# motherboard.net
KiCad netlist of a schematic drawn in EAGLE
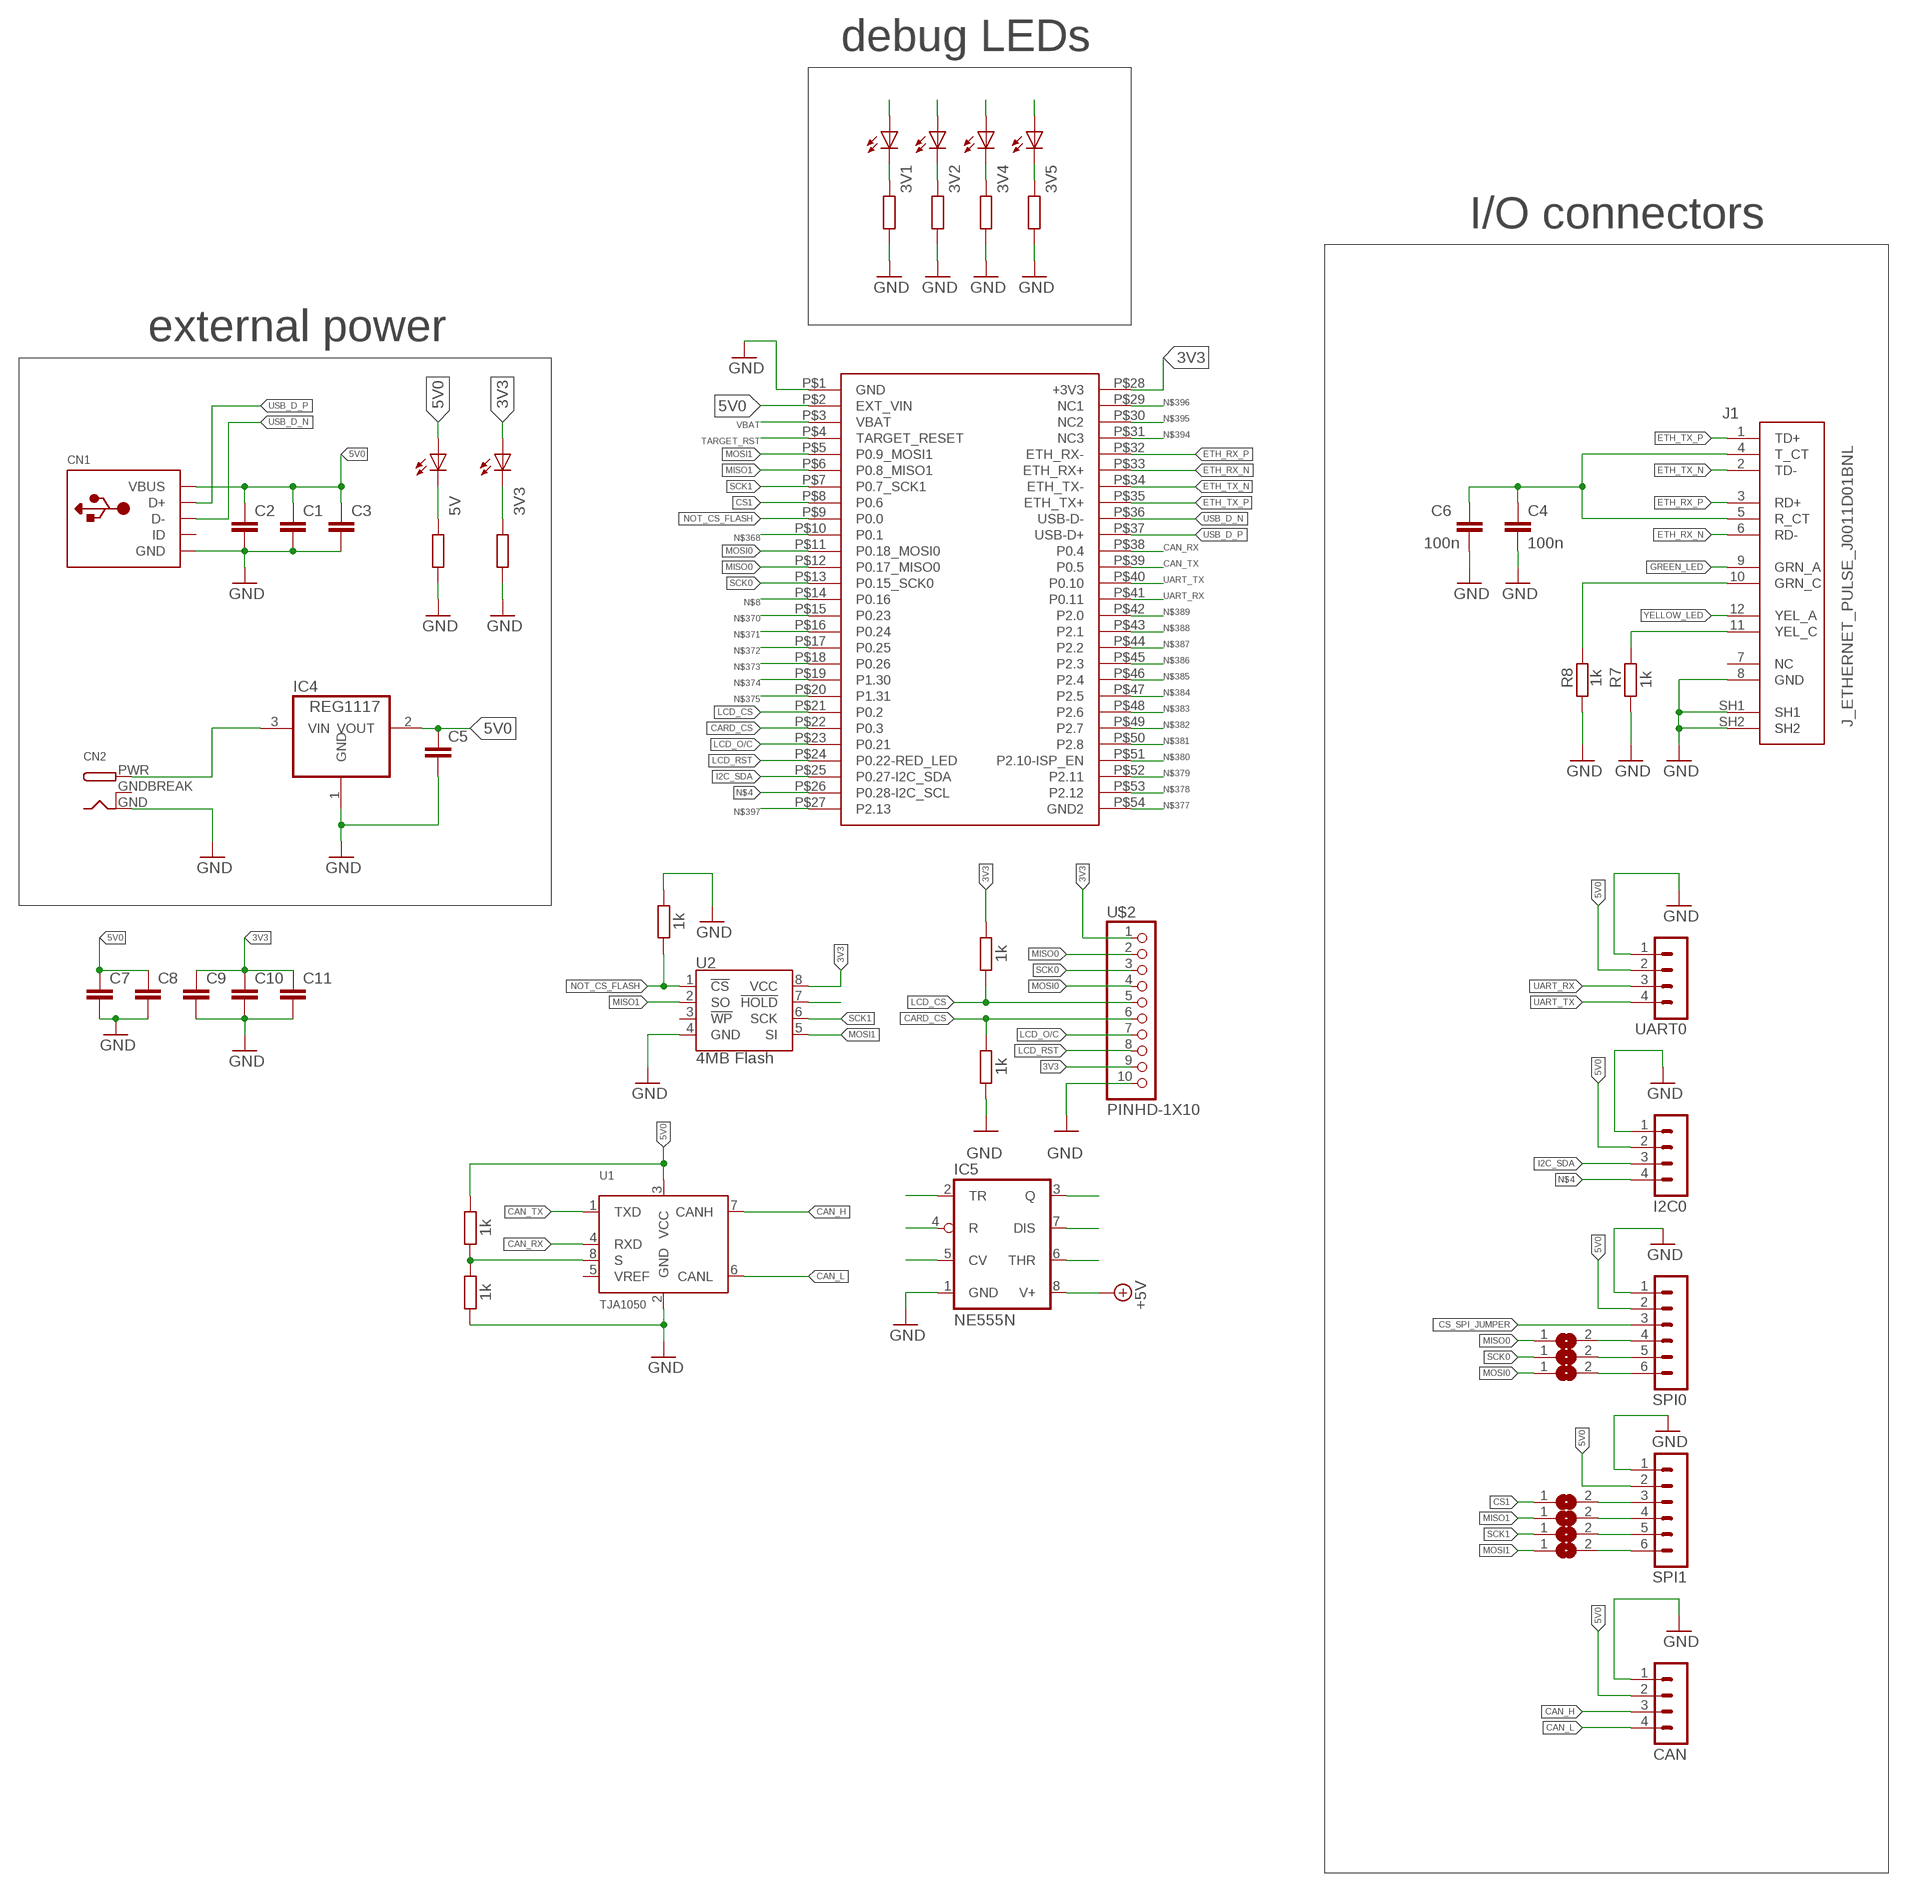
[diagram p0: schematic, sheet 1]

(export (version "E")
  (design (tool "Eeschema 10.0.6"))
  (components
    (comp (ref "3V1")
      (value "LEDCHIPLED_0805")
      (footprint "eagle-import:CHIPLED_0805")
      (libsource (lib "eagle-import") (part "LEDCHIPLED_0805"))
    )
    (comp (ref "3V2")
      (value "LEDCHIPLED_0805")
      (footprint "eagle-import:CHIPLED_0805")
      (libsource (lib "eagle-import") (part "LEDCHIPLED_0805"))
    )
    (comp (ref "3V3")
      (value "LEDCHIPLED_0805")
      (footprint "eagle-import:CHIPLED_0805")
      (libsource (lib "eagle-import") (part "LEDCHIPLED_0805"))
    )
    (comp (ref "3V4")
      (value "LEDCHIPLED_0805")
      (footprint "eagle-import:CHIPLED_0805")
      (libsource (lib "eagle-import") (part "LEDCHIPLED_0805"))
    )
    (comp (ref "3V5")
      (value "LEDCHIPLED_0805")
      (footprint "eagle-import:CHIPLED_0805")
      (libsource (lib "eagle-import") (part "LEDCHIPLED_0805"))
    )
    (comp (ref "5V")
      (value "LEDCHIPLED_0805")
      (footprint "eagle-import:CHIPLED_0805")
      (libsource (lib "eagle-import") (part "LEDCHIPLED_0805"))
    )
    (comp (ref "C1")
      (value "C-EUC0805K")
      (footprint "eagle-import:C0805K")
      (libsource (lib "eagle-import") (part "C-EUC0805K"))
    )
    (comp (ref "C2")
      (value "C-EUC0805K")
      (footprint "eagle-import:C0805K")
      (libsource (lib "eagle-import") (part "C-EUC0805K"))
    )
    (comp (ref "C3")
      (value "C-EUC0805K")
      (footprint "eagle-import:C0805K")
      (libsource (lib "eagle-import") (part "C-EUC0805K"))
    )
    (comp (ref "C4")
      (value "100n")
      (footprint "eagle-import:C0805K")
      (libsource (lib "eagle-import") (part "C-EUC0805K"))
    )
    (comp (ref "C5")
      (value "C-EUC0805K")
      (footprint "eagle-import:C0805K")
      (libsource (lib "eagle-import") (part "C-EUC0805K"))
    )
    (comp (ref "C6")
      (value "100n")
      (footprint "eagle-import:C0805K")
      (libsource (lib "eagle-import") (part "C-EUC0805K"))
    )
    (comp (ref "C7")
      (value "C-EUC0805K")
      (footprint "eagle-import:C0805K")
      (libsource (lib "eagle-import") (part "C-EUC0805K"))
    )
    (comp (ref "C8")
      (value "C-EUC0805K")
      (footprint "eagle-import:C0805K")
      (libsource (lib "eagle-import") (part "C-EUC0805K"))
    )
    (comp (ref "C9")
      (value "C-EUC0805K")
      (footprint "eagle-import:C0805K")
      (libsource (lib "eagle-import") (part "C-EUC0805K"))
    )
    (comp (ref "C10")
      (value "C-EUC0805K")
      (footprint "eagle-import:C0805K")
      (libsource (lib "eagle-import") (part "C-EUC0805K"))
    )
    (comp (ref "C11")
      (value "C-EUC0805K")
      (footprint "eagle-import:C0805K")
      (libsource (lib "eagle-import") (part "C-EUC0805K"))
    )
    (comp (ref "CAN")
      (value "MA04-1")
      (footprint "eagle-import:MA04-1")
      (libsource (lib "eagle-import") (part "MA04-1"))
    )
    (comp (ref "CN1")
      (value "USBMINIB")
      (footprint "eagle-import:USB-MINIB")
      (libsource (lib "eagle-import") (part "USBMINIB"))
    )
    (comp (ref "CN2")
      (value "DCBARRELPTH")
      (footprint "eagle-import:DCJACK_2MM_PTH")
      (libsource (lib "eagle-import") (part "DCBARRELPTH"))
    )
    (comp (ref "I2C0")
      (value "MA04-1")
      (footprint "eagle-import:MA04-1")
      (libsource (lib "eagle-import") (part "MA04-1"))
    )
    (comp (ref "IC4")
      (value "REG1117")
      (footprint "eagle-import:SOT223")
      (libsource (lib "eagle-import") (part "REG1117"))
    )
    (comp (ref "IC5")
      (value "NE555N")
      (footprint "eagle-import:DIL08")
      (libsource (lib "eagle-import") (part "555NNE"))
    )
    (comp (ref "J1")
      (value "J_ETHERNET_PULSE_J0011D01BNL")
      (footprint "eagle-import:J_ETHERNET_PULSE_J0011D01BNL")
      (libsource (lib "eagle-import") (part "J_ETHERNET_PULSE_J0011D01BNL"))
    )
    (comp (ref "R1")
      (value "1k")
      (footprint "eagle-import:R0805")
      (libsource (lib "eagle-import") (part "R-EU_R0805"))
    )
    (comp (ref "R2")
      (value "1k")
      (footprint "eagle-import:R0805")
      (libsource (lib "eagle-import") (part "R-EU_R0805"))
    )
    (comp (ref "R3")
      (value "R-EU_R0805")
      (footprint "eagle-import:R0805")
      (libsource (lib "eagle-import") (part "R-EU_R0805"))
    )
    (comp (ref "R4")
      (value "R-EU_R0805")
      (footprint "eagle-import:R0805")
      (libsource (lib "eagle-import") (part "R-EU_R0805"))
    )
    (comp (ref "R5")
      (value "1k")
      (footprint "eagle-import:R0805")
      (libsource (lib "eagle-import") (part "R-EU_R0805"))
    )
    (comp (ref "R6")
      (value "1k")
      (footprint "eagle-import:R0805")
      (libsource (lib "eagle-import") (part "R-EU_R0805"))
    )
    (comp (ref "R7")
      (value "1k")
      (footprint "eagle-import:R0805")
      (libsource (lib "eagle-import") (part "R-EU_R0805"))
    )
    (comp (ref "R8")
      (value "1k")
      (footprint "eagle-import:R0805")
      (libsource (lib "eagle-import") (part "R-EU_R0805"))
    )
    (comp (ref "R9")
      (value "R-EU_R0805")
      (footprint "eagle-import:R0805")
      (libsource (lib "eagle-import") (part "R-EU_R0805"))
    )
    (comp (ref "R10")
      (value "R-EU_R0805")
      (footprint "eagle-import:R0805")
      (libsource (lib "eagle-import") (part "R-EU_R0805"))
    )
    (comp (ref "R11")
      (value "R-EU_R0805")
      (footprint "eagle-import:R0805")
      (libsource (lib "eagle-import") (part "R-EU_R0805"))
    )
    (comp (ref "R12")
      (value "R-EU_R0805")
      (footprint "eagle-import:R0805")
      (libsource (lib "eagle-import") (part "R-EU_R0805"))
    )
    (comp (ref "R13")
      (value "1k")
      (footprint "eagle-import:R0805")
      (libsource (lib "eagle-import") (part "R-EU_R0805"))
    )
    (comp (ref "SJ1") (value "SJ") (footprint "eagle-import:SJ") (libsource (lib "eagle-import") (part "SJ")))
    (comp (ref "SJ2") (value "SJ") (footprint "eagle-import:SJ") (libsource (lib "eagle-import") (part "SJ")))
    (comp (ref "SJ3") (value "SJ") (footprint "eagle-import:SJ") (libsource (lib "eagle-import") (part "SJ")))
    (comp (ref "SJ5") (value "SJ") (footprint "eagle-import:SJ") (libsource (lib "eagle-import") (part "SJ")))
    (comp (ref "SJ6") (value "SJ") (footprint "eagle-import:SJ") (libsource (lib "eagle-import") (part "SJ")))
    (comp (ref "SJ7") (value "SJ") (footprint "eagle-import:SJ") (libsource (lib "eagle-import") (part "SJ")))
    (comp (ref "SJ8") (value "SJ") (footprint "eagle-import:SJ") (libsource (lib "eagle-import") (part "SJ")))
    (comp (ref "SPI0")
      (value "MA06-1")
      (footprint "eagle-import:MA06-1")
      (libsource (lib "eagle-import") (part "MA06-1"))
    )
    (comp (ref "SPI1")
      (value "MA06-1")
      (footprint "eagle-import:MA06-1")
      (libsource (lib "eagle-import") (part "MA06-1"))
    )
    (comp (ref "U$1")
      (value "LPC1769XPRESSO")
      (footprint "eagle-import:LPC1769XPRESSO")
      (libsource (lib "eagle-import") (part "LPC1769XPRESSO"))
    )
    (comp (ref "U$2")
      (value "PINHD-1X10")
      (footprint "eagle-import:1X10-BIG")
      (libsource (lib "eagle-import") (part "PINHD-1X10"))
    )
    (comp (ref "U1")
      (value "TJA1050")
      (footprint "eagle-import:SOT96-1")
      (libsource (lib "eagle-import") (part "TJA1050"))
    )
    (comp (ref "U2")
      (value "4MB Flash")
      (footprint "eagle-import:SO08")
      (libsource (lib "eagle-import") (part "AT25SF041"))
    )
    (comp (ref "UART0")
      (value "MA04-1")
      (footprint "eagle-import:MA04-1")
      (libsource (lib "eagle-import") (part "MA04-1"))
    )
  )
  (nets
    (net (code "1") (name "+5V") (class "Default")
      (node (ref "IC5") (pin "8") (pinfunction "V+_8") (pintype "power_in"))
    )
    (net (code "2") (name "/GNDBREAK") (class "Default")
      (node (ref "CN2") (pin "GNDBREAK") (pinfunction "GNDBREAK_GNDBREAK") (pintype "power_in"))
    )
    (net (code "3") (name "/N$8") (class "Default")
      (node (ref "U$1") (pin "P$14") (pinfunction "P0.16_P$14") (pintype "bidirectional"))
    )
    (net (code "4") (name "/N$368") (class "Default")
      (node (ref "U$1") (pin "P$10") (pinfunction "P0.1_P$10") (pintype "bidirectional"))
    )
    (net (code "5") (name "/N$370") (class "Default")
      (node (ref "U$1") (pin "P$15") (pinfunction "P0.23_P$15") (pintype "bidirectional"))
    )
    (net (code "6") (name "/N$371") (class "Default")
      (node (ref "U$1") (pin "P$16") (pinfunction "P0.24_P$16") (pintype "bidirectional"))
    )
    (net (code "7") (name "/N$372") (class "Default")
      (node (ref "U$1") (pin "P$17") (pinfunction "P0.25_P$17") (pintype "bidirectional"))
    )
    (net (code "8") (name "/N$373") (class "Default")
      (node (ref "U$1") (pin "P$18") (pinfunction "P0.26_P$18") (pintype "bidirectional"))
    )
    (net (code "9") (name "/N$374") (class "Default")
      (node (ref "U$1") (pin "P$19") (pinfunction "P1.30_P$19") (pintype "bidirectional"))
    )
    (net (code "10") (name "/N$375") (class "Default")
      (node (ref "U$1") (pin "P$20") (pinfunction "P1.31_P$20") (pintype "bidirectional"))
    )
    (net (code "11") (name "/N$377") (class "Default")
      (node (ref "U$1") (pin "P$54") (pinfunction "GND2_P$54") (pintype "bidirectional"))
    )
    (net (code "12") (name "/N$378") (class "Default")
      (node (ref "U$1") (pin "P$53") (pinfunction "P2.12_P$53") (pintype "bidirectional"))
    )
    (net (code "13") (name "/N$379") (class "Default")
      (node (ref "U$1") (pin "P$52") (pinfunction "P2.11_P$52") (pintype "bidirectional"))
    )
    (net (code "14") (name "/N$380") (class "Default")
      (node (ref "U$1") (pin "P$51") (pinfunction "P2.10-ISP_EN_P$51") (pintype "bidirectional"))
    )
    (net (code "15") (name "/N$381") (class "Default")
      (node (ref "U$1") (pin "P$50") (pinfunction "P2.8_P$50") (pintype "bidirectional"))
    )
    (net (code "16") (name "/N$382") (class "Default")
      (node (ref "U$1") (pin "P$49") (pinfunction "P2.7_P$49") (pintype "bidirectional"))
    )
    (net (code "17") (name "/N$383") (class "Default")
      (node (ref "U$1") (pin "P$48") (pinfunction "P2.6_P$48") (pintype "bidirectional"))
    )
    (net (code "18") (name "/N$384") (class "Default")
      (node (ref "U$1") (pin "P$47") (pinfunction "P2.5_P$47") (pintype "bidirectional"))
    )
    (net (code "19") (name "/N$385") (class "Default")
      (node (ref "U$1") (pin "P$46") (pinfunction "P2.4_P$46") (pintype "bidirectional"))
    )
    (net (code "20") (name "/N$386") (class "Default")
      (node (ref "U$1") (pin "P$45") (pinfunction "P2.3_P$45") (pintype "bidirectional"))
    )
    (net (code "21") (name "/N$387") (class "Default")
      (node (ref "U$1") (pin "P$44") (pinfunction "P2.2_P$44") (pintype "bidirectional"))
    )
    (net (code "22") (name "/N$388") (class "Default")
      (node (ref "U$1") (pin "P$43") (pinfunction "P2.1_P$43") (pintype "bidirectional"))
    )
    (net (code "23") (name "/N$389") (class "Default")
      (node (ref "U$1") (pin "P$42") (pinfunction "P2.0_P$42") (pintype "bidirectional"))
    )
    (net (code "24") (name "/N$394") (class "Default")
      (node (ref "U$1") (pin "P$31") (pinfunction "NC3_P$31") (pintype "bidirectional"))
    )
    (net (code "25") (name "/N$395") (class "Default")
      (node (ref "U$1") (pin "P$30") (pinfunction "NC2_P$30") (pintype "bidirectional"))
    )
    (net (code "26") (name "/N$396") (class "Default")
      (node (ref "U$1") (pin "P$29") (pinfunction "NC1_P$29") (pintype "bidirectional"))
    )
    (net (code "27") (name "/N$397") (class "Default")
      (node (ref "U$1") (pin "P$27") (pinfunction "P2.13_P$27") (pintype "bidirectional"))
    )
    (net (code "28") (name "/TARGET_RST") (class "Default")
      (node (ref "U$1") (pin "P$4") (pinfunction "TARGET_RESET_P$4") (pintype "bidirectional"))
    )
    (net (code "29") (name "/VBAT") (class "Default")
      (node (ref "U$1") (pin "P$3") (pinfunction "VBAT_P$3") (pintype "bidirectional"))
    )
    (net (code "30") (name "3V3") (class "Default")
      (node (ref "3V3") (pin "A") (pinfunction "A_A") (pintype "passive"))
      (node (ref "C10") (pin "1") (pinfunction "1_1") (pintype "passive"))
      (node (ref "C11") (pin "1") (pinfunction "1_1") (pintype "passive"))
      (node (ref "C4") (pin "1") (pinfunction "1_1") (pintype "passive"))
      (node (ref "C6") (pin "1") (pinfunction "1_1") (pintype "passive"))
      (node (ref "C9") (pin "1") (pinfunction "1_1") (pintype "passive"))
      (node (ref "J1") (pin "4") (pinfunction "T_CT_4") (pintype "passive"))
      (node (ref "J1") (pin "5") (pinfunction "R_CT_5") (pintype "passive"))
      (node (ref "R1") (pin "2") (pinfunction "2_2") (pintype "passive"))
      (node (ref "U$1") (pin "P$28") (pinfunction "+3V3_P$28") (pintype "bidirectional"))
      (node (ref "U$2") (pin "1") (pinfunction "1_1") (pintype "passive"))
      (node (ref "U$2") (pin "9") (pinfunction "9_9") (pintype "passive"))
      (node (ref "U2") (pin "8") (pinfunction "VCC_8") (pintype "bidirectional"))
    )
    (net (code "31") (name "5V0") (class "Default")
      (node (ref "5V") (pin "A") (pinfunction "A_A") (pintype "passive"))
      (node (ref "C1") (pin "1") (pinfunction "1_1") (pintype "passive"))
      (node (ref "C2") (pin "1") (pinfunction "1_1") (pintype "passive"))
      (node (ref "C3") (pin "1") (pinfunction "1_1") (pintype "passive"))
      (node (ref "C5") (pin "1") (pinfunction "1_1") (pintype "passive"))
      (node (ref "C7") (pin "1") (pinfunction "1_1") (pintype "passive"))
      (node (ref "C8") (pin "1") (pinfunction "1_1") (pintype "passive"))
      (node (ref "CAN") (pin "2") (pinfunction "2_2") (pintype "passive"))
      (node (ref "CN1") (pin "VBUS") (pinfunction "VBUS_VBUS") (pintype "power_in"))
      (node (ref "I2C0") (pin "2") (pinfunction "2_2") (pintype "passive"))
      (node (ref "IC4") (pin "2") (pinfunction "VOUT_2") (pintype "output"))
      (node (ref "R6") (pin "2") (pinfunction "2_2") (pintype "passive"))
      (node (ref "SPI0") (pin "2") (pinfunction "2_2") (pintype "passive"))
      (node (ref "SPI1") (pin "2") (pinfunction "2_2") (pintype "passive"))
      (node (ref "U$1") (pin "P$2") (pinfunction "EXT_VIN_P$2") (pintype "bidirectional"))
      (node (ref "U1") (pin "3") (pinfunction "VCC_3") (pintype "bidirectional"))
      (node (ref "UART0") (pin "2") (pinfunction "2_2") (pintype "passive"))
    )
    (net (code "32") (name "CAN_H") (class "Default")
      (node (ref "CAN") (pin "3") (pinfunction "3_3") (pintype "passive"))
      (node (ref "U1") (pin "7") (pinfunction "CANH_7") (pintype "bidirectional"))
    )
    (net (code "33") (name "CAN_L") (class "Default")
      (node (ref "CAN") (pin "4") (pinfunction "4_4") (pintype "passive"))
      (node (ref "U1") (pin "6") (pinfunction "CANL_6") (pintype "bidirectional"))
    )
    (net (code "34") (name "CAN_RX") (class "Default")
      (node (ref "U$1") (pin "P$38") (pinfunction "P0.4_P$38") (pintype "bidirectional"))
      (node (ref "U1") (pin "4") (pinfunction "RXD_4") (pintype "bidirectional"))
    )
    (net (code "35") (name "CAN_TX") (class "Default")
      (node (ref "U$1") (pin "P$39") (pinfunction "P0.5_P$39") (pintype "bidirectional"))
      (node (ref "U1") (pin "1") (pinfunction "TXD_1") (pintype "output"))
    )
    (net (code "36") (name "CARD_CS") (class "Default")
      (node (ref "R2") (pin "2") (pinfunction "2_2") (pintype "passive"))
      (node (ref "U$1") (pin "P$22") (pinfunction "P0.3_P$22") (pintype "bidirectional"))
      (node (ref "U$2") (pin "6") (pinfunction "6_6") (pintype "passive"))
    )
    (net (code "37") (name "CS1") (class "Default")
      (node (ref "SJ8") (pin "1") (pinfunction "1_1") (pintype "passive"))
      (node (ref "U$1") (pin "P$8") (pinfunction "P0.6_P$8") (pintype "bidirectional"))
    )
    (net (code "38") (name "CS_SPI_JUMPER") (class "Default")
      (node (ref "SPI0") (pin "3") (pinfunction "3_3") (pintype "passive"))
    )
    (net (code "39") (name "ETH_RX_N") (class "Default")
      (node (ref "J1") (pin "6") (pinfunction "RD-_6") (pintype "passive"))
      (node (ref "U$1") (pin "P$33") (pinfunction "ETH_RX+_P$33") (pintype "bidirectional"))
    )
    (net (code "40") (name "ETH_RX_P") (class "Default")
      (node (ref "J1") (pin "3") (pinfunction "RD+_3") (pintype "passive"))
      (node (ref "U$1") (pin "P$32") (pinfunction "ETH_RX-_P$32") (pintype "bidirectional"))
    )
    (net (code "41") (name "ETH_TX_N") (class "Default")
      (node (ref "J1") (pin "2") (pinfunction "TD-_2") (pintype "passive"))
      (node (ref "U$1") (pin "P$34") (pinfunction "ETH_TX-_P$34") (pintype "bidirectional"))
    )
    (net (code "42") (name "ETH_TX_P") (class "Default")
      (node (ref "J1") (pin "1") (pinfunction "TD+_1") (pintype "passive"))
      (node (ref "U$1") (pin "P$35") (pinfunction "ETH_TX+_P$35") (pintype "bidirectional"))
    )
    (net (code "43") (name "GND") (class "Default")
      (node (ref "C1") (pin "2") (pinfunction "2_2") (pintype "passive"))
      (node (ref "C10") (pin "2") (pinfunction "2_2") (pintype "passive"))
      (node (ref "C11") (pin "2") (pinfunction "2_2") (pintype "passive"))
      (node (ref "C2") (pin "2") (pinfunction "2_2") (pintype "passive"))
      (node (ref "C3") (pin "2") (pinfunction "2_2") (pintype "passive"))
      (node (ref "C4") (pin "2") (pinfunction "2_2") (pintype "passive"))
      (node (ref "C5") (pin "2") (pinfunction "2_2") (pintype "passive"))
      (node (ref "C6") (pin "2") (pinfunction "2_2") (pintype "passive"))
      (node (ref "C7") (pin "2") (pinfunction "2_2") (pintype "passive"))
      (node (ref "C8") (pin "2") (pinfunction "2_2") (pintype "passive"))
      (node (ref "C9") (pin "2") (pinfunction "2_2") (pintype "passive"))
      (node (ref "CAN") (pin "1") (pinfunction "1_1") (pintype "passive"))
      (node (ref "CN1") (pin "GND") (pinfunction "GND_GND") (pintype "power_in"))
      (node (ref "CN2") (pin "GND") (pinfunction "GND_GND") (pintype "power_in"))
      (node (ref "I2C0") (pin "1") (pinfunction "1_1") (pintype "passive"))
      (node (ref "IC4") (pin "1") (pinfunction "GND_1") (pintype "power_in"))
      (node (ref "IC5") (pin "1") (pinfunction "GND_1") (pintype "power_in"))
      (node (ref "J1") (pin "8") (pinfunction "GND_8") (pintype "power_in"))
      (node (ref "J1") (pin "SH1") (pinfunction "SH1_SH1") (pintype "power_in"))
      (node (ref "J1") (pin "SH2") (pinfunction "SH2_SH2") (pintype "power_in"))
      (node (ref "R10") (pin "1") (pinfunction "1_1") (pintype "passive"))
      (node (ref "R11") (pin "1") (pinfunction "1_1") (pintype "passive"))
      (node (ref "R12") (pin "1") (pinfunction "1_1") (pintype "passive"))
      (node (ref "R13") (pin "1") (pinfunction "1_1") (pintype "passive"))
      (node (ref "R2") (pin "1") (pinfunction "1_1") (pintype "passive"))
      (node (ref "R3") (pin "1") (pinfunction "1_1") (pintype "passive"))
      (node (ref "R4") (pin "1") (pinfunction "1_1") (pintype "passive"))
      (node (ref "R5") (pin "2") (pinfunction "2_2") (pintype "passive"))
      (node (ref "R7") (pin "1") (pinfunction "1_1") (pintype "passive"))
      (node (ref "R8") (pin "1") (pinfunction "1_1") (pintype "passive"))
      (node (ref "R9") (pin "1") (pinfunction "1_1") (pintype "passive"))
      (node (ref "SPI0") (pin "1") (pinfunction "1_1") (pintype "passive"))
      (node (ref "SPI1") (pin "1") (pinfunction "1_1") (pintype "passive"))
      (node (ref "U$1") (pin "P$1") (pinfunction "GND_P$1") (pintype "bidirectional"))
      (node (ref "U$2") (pin "10") (pinfunction "10_10") (pintype "passive"))
      (node (ref "U1") (pin "2") (pinfunction "GND_2") (pintype "bidirectional"))
      (node (ref "U2") (pin "4") (pinfunction "GND_4") (pintype "bidirectional"))
      (node (ref "UART0") (pin "1") (pinfunction "1_1") (pintype "passive"))
    )
    (net (code "44") (name "GREEN_LED") (class "Default")
      (node (ref "J1") (pin "9") (pinfunction "GRN_A_9") (pintype "passive"))
    )
    (net (code "45") (name "I2C_SDA") (class "Default")
      (node (ref "I2C0") (pin "3") (pinfunction "3_3") (pintype "passive"))
      (node (ref "U$1") (pin "P$25") (pinfunction "P0.27-I2C_SDA_P$25") (pintype "bidirectional"))
    )
    (net (code "46") (name "LCD_CS") (class "Default")
      (node (ref "R1") (pin "1") (pinfunction "1_1") (pintype "passive"))
      (node (ref "U$1") (pin "P$21") (pinfunction "P0.2_P$21") (pintype "bidirectional"))
      (node (ref "U$2") (pin "5") (pinfunction "5_5") (pintype "passive"))
    )
    (net (code "47") (name "LCD_O{slash}C") (class "Default")
      (node (ref "U$1") (pin "P$23") (pinfunction "P0.21_P$23") (pintype "bidirectional"))
      (node (ref "U$2") (pin "7") (pinfunction "7_7") (pintype "passive"))
    )
    (net (code "48") (name "LCD_RST") (class "Default")
      (node (ref "U$1") (pin "P$24") (pinfunction "P0.22-RED_LED_P$24") (pintype "bidirectional"))
      (node (ref "U$2") (pin "8") (pinfunction "8_8") (pintype "passive"))
    )
    (net (code "49") (name "MISO0") (class "Default")
      (node (ref "SJ3") (pin "1") (pinfunction "1_1") (pintype "passive"))
      (node (ref "U$1") (pin "P$12") (pinfunction "P0.17_MISO0_P$12") (pintype "bidirectional"))
      (node (ref "U$2") (pin "2") (pinfunction "2_2") (pintype "passive"))
    )
    (net (code "50") (name "MISO1") (class "Default")
      (node (ref "SJ7") (pin "1") (pinfunction "1_1") (pintype "passive"))
      (node (ref "U$1") (pin "P$6") (pinfunction "P0.8_MISO1_P$6") (pintype "bidirectional"))
      (node (ref "U2") (pin "2") (pinfunction "SO_2") (pintype "bidirectional"))
    )
    (net (code "51") (name "MOSI0") (class "Default")
      (node (ref "SJ1") (pin "1") (pinfunction "1_1") (pintype "passive"))
      (node (ref "U$1") (pin "P$11") (pinfunction "P0.18_MOSI0_P$11") (pintype "bidirectional"))
      (node (ref "U$2") (pin "4") (pinfunction "4_4") (pintype "passive"))
    )
    (net (code "52") (name "MOSI1") (class "Default")
      (node (ref "SJ5") (pin "1") (pinfunction "1_1") (pintype "passive"))
      (node (ref "U$1") (pin "P$5") (pinfunction "P0.9_MOSI1_P$5") (pintype "bidirectional"))
      (node (ref "U2") (pin "5") (pinfunction "SI_5") (pintype "bidirectional"))
    )
    (net (code "53") (name "N$4") (class "Default")
      (node (ref "I2C0") (pin "4") (pinfunction "4_4") (pintype "passive"))
      (node (ref "U$1") (pin "P$26") (pinfunction "P0.28-I2C_SCL_P$26") (pintype "bidirectional"))
    )
    (net (code "54") (name "NOT_CS_FLASH") (class "Default")
      (node (ref "R5") (pin "1") (pinfunction "1_1") (pintype "passive"))
      (node (ref "U$1") (pin "P$9") (pinfunction "P0.0_P$9") (pintype "bidirectional"))
      (node (ref "U2") (pin "1") (pinfunction "~{CS}_1") (pintype "bidirectional"))
    )
    (net (code "55") (name "Net-(3V1-PadC)") (class "Default")
      (node (ref "3V1") (pin "C") (pinfunction "C_C") (pintype "passive"))
      (node (ref "R9") (pin "2") (pinfunction "2_2") (pintype "passive"))
    )
    (net (code "56") (name "Net-(3V2-PadC)") (class "Default")
      (node (ref "3V2") (pin "C") (pinfunction "C_C") (pintype "passive"))
      (node (ref "R10") (pin "2") (pinfunction "2_2") (pintype "passive"))
    )
    (net (code "57") (name "Net-(3V3-PadC)") (class "Default")
      (node (ref "3V3") (pin "C") (pinfunction "C_C") (pintype "passive"))
      (node (ref "R4") (pin "2") (pinfunction "2_2") (pintype "passive"))
    )
    (net (code "58") (name "Net-(3V4-PadC)") (class "Default")
      (node (ref "3V4") (pin "C") (pinfunction "C_C") (pintype "passive"))
      (node (ref "R11") (pin "2") (pinfunction "2_2") (pintype "passive"))
    )
    (net (code "59") (name "Net-(3V5-PadC)") (class "Default")
      (node (ref "3V5") (pin "C") (pinfunction "C_C") (pintype "passive"))
      (node (ref "R12") (pin "2") (pinfunction "2_2") (pintype "passive"))
    )
    (net (code "60") (name "Net-(5V-PadC)") (class "Default")
      (node (ref "5V") (pin "C") (pinfunction "C_C") (pintype "passive"))
      (node (ref "R3") (pin "2") (pinfunction "2_2") (pintype "passive"))
    )
    (net (code "61") (name "Net-(IC4-VIN)") (class "Default")
      (node (ref "CN2") (pin "PWR") (pinfunction "PWR_PWR") (pintype "power_in"))
      (node (ref "IC4") (pin "3") (pinfunction "VIN_3") (pintype "input"))
    )
    (net (code "62") (name "Net-(J1-GRN_C)") (class "Default")
      (node (ref "J1") (pin "10") (pinfunction "GRN_C_10") (pintype "passive"))
      (node (ref "R8") (pin "2") (pinfunction "2_2") (pintype "passive"))
    )
    (net (code "63") (name "Net-(J1-YEL_C)") (class "Default")
      (node (ref "J1") (pin "11") (pinfunction "YEL_C_11") (pintype "passive"))
      (node (ref "R7") (pin "2") (pinfunction "2_2") (pintype "passive"))
    )
    (net (code "64") (name "Net-(SJ1-Pad2)") (class "Default")
      (node (ref "SJ1") (pin "2") (pinfunction "2_2") (pintype "passive"))
      (node (ref "SPI0") (pin "6") (pinfunction "6_6") (pintype "passive"))
    )
    (net (code "65") (name "Net-(SJ2-Pad2)") (class "Default")
      (node (ref "SJ2") (pin "2") (pinfunction "2_2") (pintype "passive"))
      (node (ref "SPI0") (pin "5") (pinfunction "5_5") (pintype "passive"))
    )
    (net (code "66") (name "Net-(SJ3-Pad2)") (class "Default")
      (node (ref "SJ3") (pin "2") (pinfunction "2_2") (pintype "passive"))
      (node (ref "SPI0") (pin "4") (pinfunction "4_4") (pintype "passive"))
    )
    (net (code "67") (name "Net-(SJ5-Pad2)") (class "Default")
      (node (ref "SJ5") (pin "2") (pinfunction "2_2") (pintype "passive"))
      (node (ref "SPI1") (pin "6") (pinfunction "6_6") (pintype "passive"))
    )
    (net (code "68") (name "Net-(SJ6-Pad2)") (class "Default")
      (node (ref "SJ6") (pin "2") (pinfunction "2_2") (pintype "passive"))
      (node (ref "SPI1") (pin "5") (pinfunction "5_5") (pintype "passive"))
    )
    (net (code "69") (name "Net-(SJ7-Pad2)") (class "Default")
      (node (ref "SJ7") (pin "2") (pinfunction "2_2") (pintype "passive"))
      (node (ref "SPI1") (pin "4") (pinfunction "4_4") (pintype "passive"))
    )
    (net (code "70") (name "Net-(SJ8-Pad2)") (class "Default")
      (node (ref "SJ8") (pin "2") (pinfunction "2_2") (pintype "passive"))
      (node (ref "SPI1") (pin "3") (pinfunction "3_3") (pintype "passive"))
    )
    (net (code "71") (name "Net-(U1-S)") (class "Default")
      (node (ref "R13") (pin "2") (pinfunction "2_2") (pintype "passive"))
      (node (ref "R6") (pin "1") (pinfunction "1_1") (pintype "passive"))
      (node (ref "U1") (pin "8") (pinfunction "S_8") (pintype "power_in"))
    )
    (net (code "72") (name "SCK0") (class "Default")
      (node (ref "SJ2") (pin "1") (pinfunction "1_1") (pintype "passive"))
      (node (ref "U$1") (pin "P$13") (pinfunction "P0.15_SCK0_P$13") (pintype "bidirectional"))
      (node (ref "U$2") (pin "3") (pinfunction "3_3") (pintype "passive"))
    )
    (net (code "73") (name "SCK1") (class "Default")
      (node (ref "SJ6") (pin "1") (pinfunction "1_1") (pintype "passive"))
      (node (ref "U$1") (pin "P$7") (pinfunction "P0.7_SCK1_P$7") (pintype "bidirectional"))
      (node (ref "U2") (pin "6") (pinfunction "SCK_6") (pintype "bidirectional"))
    )
    (net (code "74") (name "UART_RX") (class "Default")
      (node (ref "U$1") (pin "P$41") (pinfunction "P0.11_P$41") (pintype "bidirectional"))
      (node (ref "UART0") (pin "3") (pinfunction "3_3") (pintype "passive"))
    )
    (net (code "75") (name "UART_TX") (class "Default")
      (node (ref "U$1") (pin "P$40") (pinfunction "P0.10_P$40") (pintype "bidirectional"))
      (node (ref "UART0") (pin "4") (pinfunction "4_4") (pintype "passive"))
    )
    (net (code "76") (name "USB_D_N") (class "Default")
      (node (ref "CN1") (pin "D-") (pinfunction "D-_D-") (pintype "bidirectional"))
      (node (ref "U$1") (pin "P$36") (pinfunction "USB-D-_P$36") (pintype "bidirectional"))
    )
    (net (code "77") (name "USB_D_P") (class "Default")
      (node (ref "CN1") (pin "D+") (pinfunction "D+_D+") (pintype "bidirectional"))
      (node (ref "U$1") (pin "P$37") (pinfunction "USB-D+_P$37") (pintype "bidirectional"))
    )
    (net (code "78") (name "YELLOW_LED") (class "Default")
      (node (ref "J1") (pin "12") (pinfunction "YEL_A_12") (pintype "passive"))
    )
    (net (code "79") (name "unconnected-(3V1-PadA)") (class "Default")
      (node (ref "3V1") (pin "A") (pinfunction "A_A") (pintype "passive"))
    )
    (net (code "80") (name "unconnected-(3V2-PadA)") (class "Default")
      (node (ref "3V2") (pin "A") (pinfunction "A_A") (pintype "passive"))
    )
    (net (code "81") (name "unconnected-(3V4-PadA)") (class "Default")
      (node (ref "3V4") (pin "A") (pinfunction "A_A") (pintype "passive"))
    )
    (net (code "82") (name "unconnected-(3V5-PadA)") (class "Default")
      (node (ref "3V5") (pin "A") (pinfunction "A_A") (pintype "passive"))
    )
    (net (code "83") (name "unconnected-(CN1-PadID)") (class "Default")
      (node (ref "CN1") (pin "ID") (pinfunction "ID_ID") (pintype "bidirectional"))
    )
    (net (code "84") (name "unconnected-(IC5-CV-Pad5)") (class "Default")
      (node (ref "IC5") (pin "5") (pinfunction "CV_5") (pintype "input"))
    )
    (net (code "85") (name "unconnected-(IC5-DIS-Pad7)") (class "Default")
      (node (ref "IC5") (pin "7") (pinfunction "DIS_7") (pintype "input"))
    )
    (net (code "86") (name "unconnected-(IC5-Q-Pad3)") (class "Default")
      (node (ref "IC5") (pin "3") (pinfunction "Q_3") (pintype "output"))
    )
    (net (code "87") (name "unconnected-(IC5-R-Pad4)") (class "Default")
      (node (ref "IC5") (pin "4") (pinfunction "R_4") (pintype "input"))
    )
    (net (code "88") (name "unconnected-(IC5-THR-Pad6)") (class "Default")
      (node (ref "IC5") (pin "6") (pinfunction "THR_6") (pintype "input"))
    )
    (net (code "89") (name "unconnected-(IC5-TR-Pad2)") (class "Default")
      (node (ref "IC5") (pin "2") (pinfunction "TR_2") (pintype "input"))
    )
    (net (code "90") (name "unconnected-(J1-NC-Pad7)") (class "Default")
      (node (ref "J1") (pin "7") (pinfunction "NC_7") (pintype "no_connect"))
    )
    (net (code "91") (name "unconnected-(U1-VREF-Pad5)") (class "Default")
      (node (ref "U1") (pin "5") (pinfunction "VREF_5") (pintype "passive"))
    )
    (net (code "92") (name "unconnected-(U2-~{HOLD}-Pad7)") (class "Default")
      (node (ref "U2") (pin "7") (pinfunction "~{HOLD}_7") (pintype "bidirectional"))
    )
    (net (code "93") (name "unconnected-(U2-~{WP}-Pad3)") (class "Default")
      (node (ref "U2") (pin "3") (pinfunction "~{WP}_3") (pintype "bidirectional"))
    )
  )
)
